# SD.net
KiCad netlist of a schematic drawn in Altium Designer
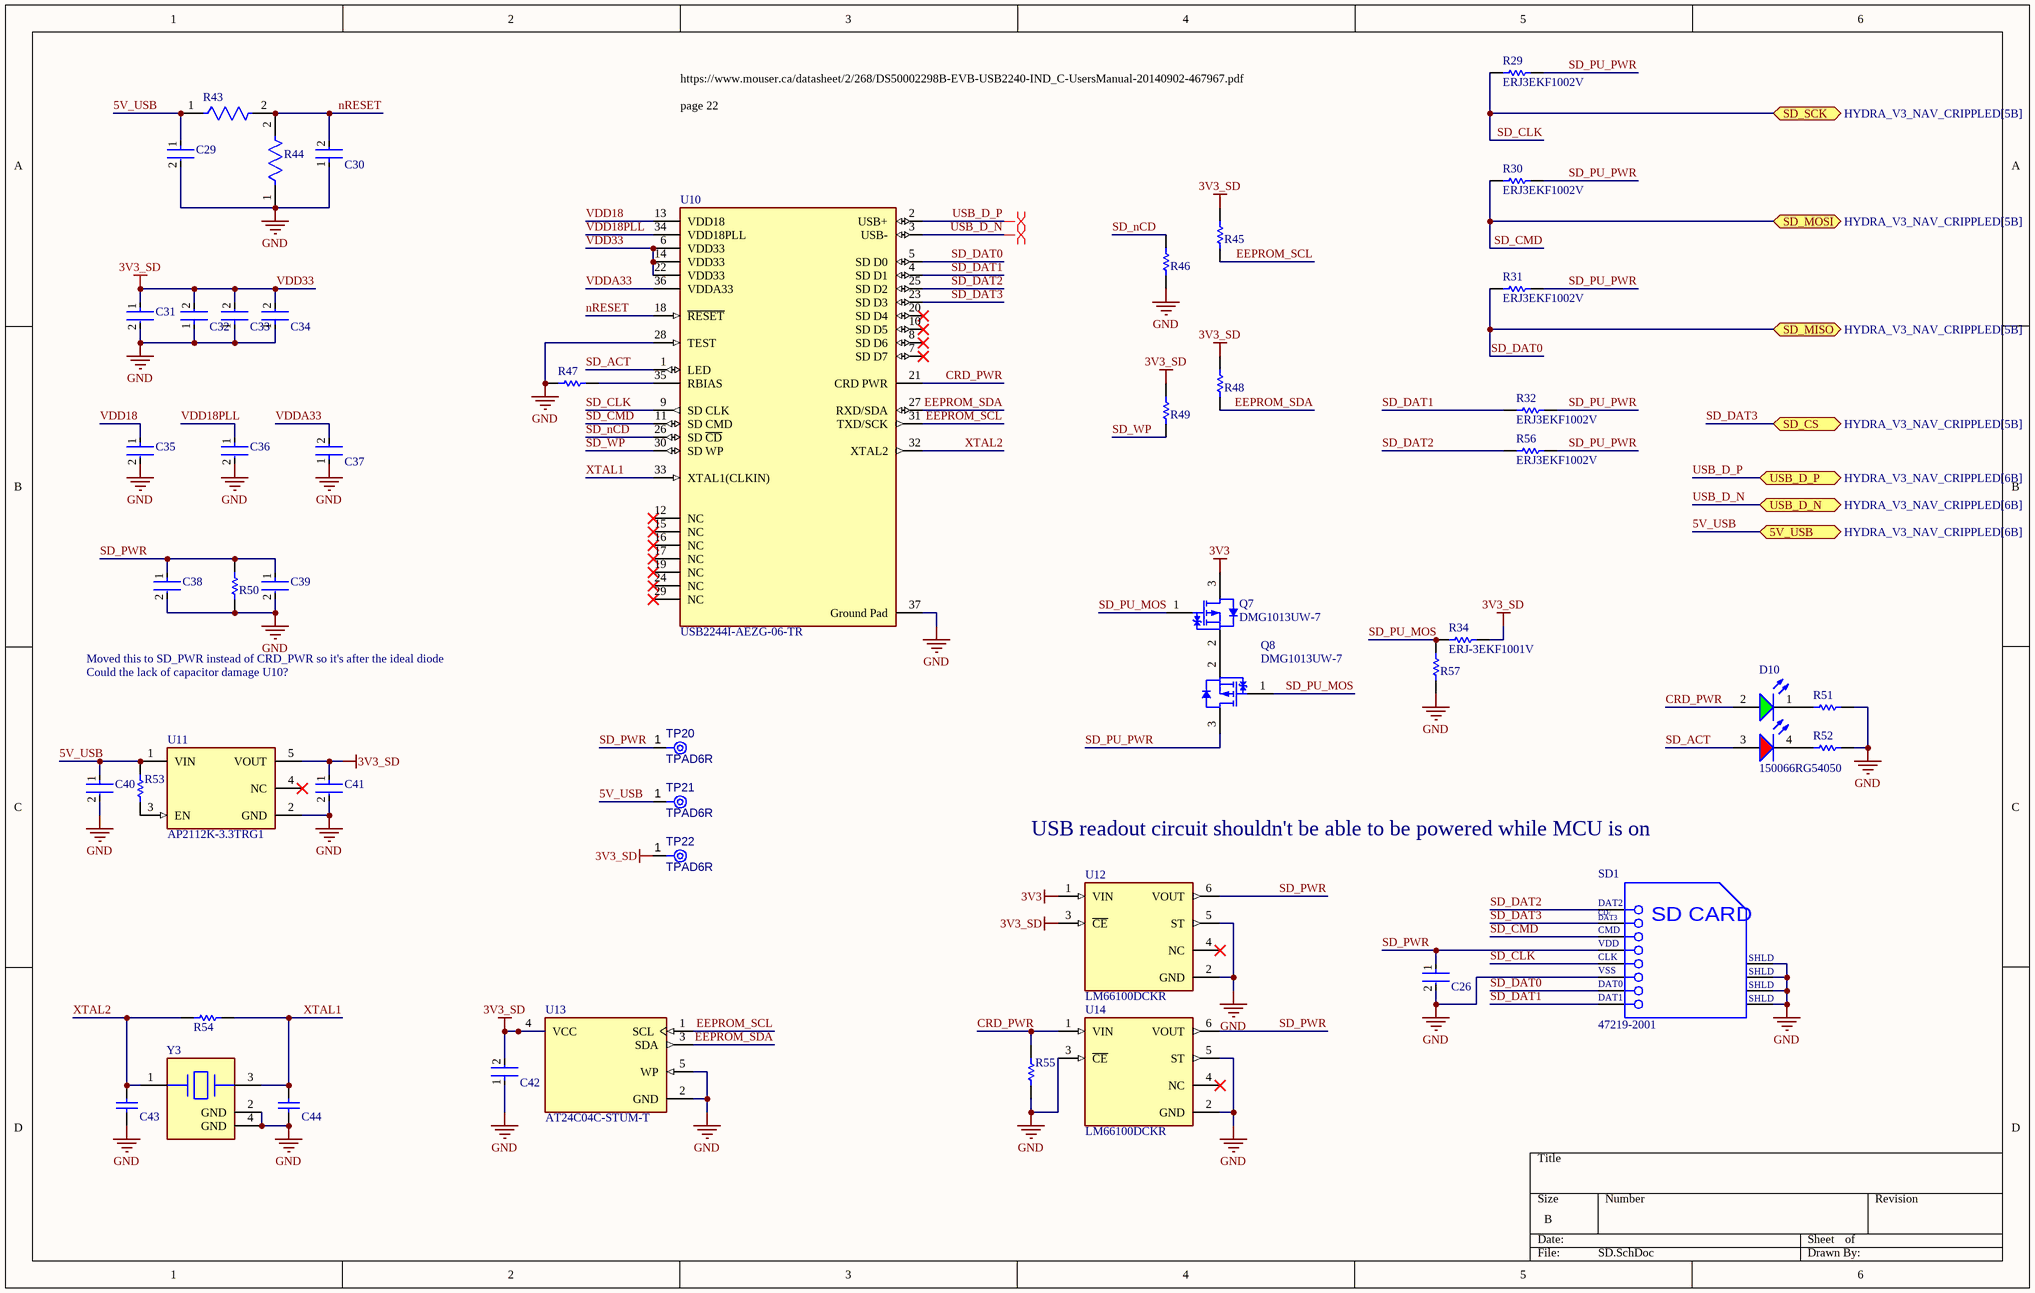
[diagram p0: SD.SchDoc]

(export (version "E")
  (design (tool "Eeschema 10.0.6"))
  (components
    (comp (ref "C26")
      (value "C0402C104K8PACTU")
      (footprint "FP-C0402-BB-MFG")
      (description "CAP CER 0.1UF 10V X5R 0402")
      (fields (field (name "MANUFACTURER") "Kemet") (field (name "TOLERANCE") "0.1"))
      (libsource (lib "Altium Content Vault") (part "b4654b650e69147ec39a6b967a45e02"))
    )
    (comp (ref "C29")
      (value "CC0603KRX7R7BB105")
      (footprint "FP-CC0603-DA-MFG")
      (description "CAP CER 1UF 16V X7R 0603")
      (fields (field (name "TOLERANCE") "0.1") (field (name "MANUFACTURER") "YAGEO"))
      (libsource (lib "Altium Content Vault") (part "11868f565c42a9108669ba33697ecf6"))
    )
    (comp (ref "C30")
      (value "C0402C104K8PACTU")
      (footprint "FP-C0402-BB-MFG")
      (description "CAP CER 0.1UF 10V X5R 0402")
      (fields (field (name "MANUFACTURER") "Kemet") (field (name "TOLERANCE") "0.1"))
      (libsource (lib "Altium Content Vault") (part "b4654b650e69147ec39a6b967a45e02"))
    )
    (comp (ref "C31")
      (value "C0603C475K9PACTU")
      (footprint "FP-C0603-CG-MFG")
      (description "CAP CER 4.7UF 6.3V X5R 0603")
      (fields (field (name "TOLERANCE") "10%") (field (name "MANUFACTURER") "Kemet"))
      (libsource (lib "Altium Content Vault") (part "11868f565c42a9108669ba33697ecf6"))
    )
    (comp (ref "C32")
      (value "C0402C104K8PACTU")
      (footprint "FP-C0402-BB-MFG")
      (description "CAP CER 0.1UF 10V X5R 0402")
      (fields (field (name "MANUFACTURER") "Kemet") (field (name "TOLERANCE") "0.1"))
      (libsource (lib "Altium Content Vault") (part "b4654b650e69147ec39a6b967a45e02"))
    )
    (comp (ref "C33")
      (value "C0402C104K8PACTU")
      (footprint "FP-C0402-BB-MFG")
      (description "CAP CER 0.1UF 10V X5R 0402")
      (fields (field (name "MANUFACTURER") "Kemet") (field (name "TOLERANCE") "0.1"))
      (libsource (lib "Altium Content Vault") (part "b4654b650e69147ec39a6b967a45e02"))
    )
    (comp (ref "C34")
      (value "C0402C104K8PACTU")
      (footprint "FP-C0402-BB-MFG")
      (description "CAP CER 0.1UF 10V X5R 0402")
      (fields (field (name "MANUFACTURER") "Kemet") (field (name "TOLERANCE") "0.1"))
      (libsource (lib "Altium Content Vault") (part "b4654b650e69147ec39a6b967a45e02"))
    )
    (comp (ref "C35")
      (value "CC0603KRX7R7BB105")
      (footprint "FP-CC0603-DA-MFG")
      (description "CAP CER 1UF 16V X7R 0603")
      (fields (field (name "TOLERANCE") "0.1") (field (name "MANUFACTURER") "YAGEO"))
      (libsource (lib "Altium Content Vault") (part "11868f565c42a9108669ba33697ecf6"))
    )
    (comp (ref "C36")
      (value "CC0603KRX7R7BB105")
      (footprint "FP-CC0603-DA-MFG")
      (description "CAP CER 1UF 16V X7R 0603")
      (fields (field (name "TOLERANCE") "0.1") (field (name "MANUFACTURER") "YAGEO"))
      (libsource (lib "Altium Content Vault") (part "11868f565c42a9108669ba33697ecf6"))
    )
    (comp (ref "C37")
      (value "C0402C104K8PACTU")
      (footprint "FP-C0402-BB-MFG")
      (description "CAP CER 0.1UF 10V X5R 0402")
      (fields (field (name "MANUFACTURER") "Kemet") (field (name "TOLERANCE") "0.1"))
      (libsource (lib "Altium Content Vault") (part "b4654b650e69147ec39a6b967a45e02"))
    )
    (comp (ref "C38")
      (value "C0603C475K9PACTU")
      (footprint "FP-C0603-CG-MFG")
      (description "CAP CER 4.7UF 6.3V X5R 0603")
      (fields (field (name "TOLERANCE") "10%") (field (name "MANUFACTURER") "Kemet"))
      (libsource (lib "Altium Content Vault") (part "11868f565c42a9108669ba33697ecf6"))
    )
    (comp (ref "C39")
      (value "CC0603KRX7R9BB102")
      (footprint "FP-CC0603-DA-MFG")
      (description "CAP CER 1000PF 50V X7R 0603")
      (fields
        (field (name "MANUFACTURER") "YAGEO")
        (field (name "OCTOPART") "https://octopart.com/cc0603krx7r9bb102-yageo-192933")
      )
      (libsource (lib "Altium Content Vault") (part "11868f565c42a9108669ba33697ecf6"))
    )
    (comp (ref "C40")
      (value "CC0603KRX7R7BB105")
      (footprint "FP-CC0603-DA-MFG")
      (description "CAP CER 1UF 16V X7R 0603")
      (fields (field (name "TOLERANCE") "0.1") (field (name "MANUFACTURER") "YAGEO"))
      (libsource (lib "Altium Content Vault") (part "11868f565c42a9108669ba33697ecf6"))
    )
    (comp (ref "C41")
      (value "CC0603KRX7R7BB105")
      (footprint "FP-CC0603-DA-MFG")
      (description "CAP CER 1UF 16V X7R 0603")
      (fields (field (name "TOLERANCE") "0.1") (field (name "MANUFACTURER") "YAGEO"))
      (libsource (lib "Altium Content Vault") (part "11868f565c42a9108669ba33697ecf6"))
    )
    (comp (ref "C42")
      (value "C0402C104K8PACTU")
      (footprint "FP-C0402-BB-MFG")
      (description "CAP CER 0.1UF 10V X5R 0402")
      (fields (field (name "MANUFACTURER") "Kemet") (field (name "TOLERANCE") "0.1"))
      (libsource (lib "Altium Content Vault") (part "b4654b650e69147ec39a6b967a45e02"))
    )
    (comp (ref "C43")
      (value "CC0603JRNPO9BN180")
      (footprint "CAPC1608X90X40LL10T20")
      (description "Chip Capacitor, 18 pF, +/- 5%, 50 V, -55 to 125 degC, 0603 (1608 Metric), RoHS, Tape and Reel")
      (fields (field (name "TOLERANCE") "1%"))
      (libsource (lib "Altium Content Vault") (part "CAP-NP-2"))
    )
    (comp (ref "C44")
      (value "CC0603JRNPO9BN180")
      (footprint "CAPC1608X90X40LL10T20")
      (description "Chip Capacitor, 18 pF, +/- 5%, 50 V, -55 to 125 degC, 0603 (1608 Metric), RoHS, Tape and Reel")
      (fields (field (name "TOLERANCE") "1%"))
      (libsource (lib "Altium Content Vault") (part "CAP-NP-2"))
    )
    (comp (ref "D10")
      (value "150066RG54050")
      (footprint "WL-SBCD_0606")
      (description "Led, Red/Grn, 180Mcd/230Mcd, 624Nm/525Nm Rohs Compliant: Yes")
      (libsource (lib "uORocketry Hardware") (part "WL-SBCD_0606_Red & Green"))
    )
    (comp (ref "Q7")
      (value "DMG1013UW-7")
      (footprint "DIOD-SOT323-3_V")
      (fields (field (name "MANUFACTURER") "Diodes Inc"))
      (libsource (lib "Altium Content Vault") (part "PEMOS-GSD-3_C"))
    )
    (comp (ref "Q8")
      (value "DMG1013UW-7")
      (footprint "DIOD-SOT323-3_V")
      (fields (field (name "MANUFACTURER") "Diodes Inc"))
      (libsource (lib "Altium Content Vault") (part "PEMOS-GSD-3_C"))
    )
    (comp (ref "R29")
      (value "ERJ3EKF1002V")
      (footprint "RESC1609X55X30LL15T15")
      (description "Chip Resistor, 10 KOhm, +/- 1%, 0.1 W, -55 to 155 degC, 0603 (1608 Metric), RoHS, Tape and Reel")
      (fields (field (name "TOLERANCE") "1%") (field (name "MANUFACTURER") "Panasonic"))
      (libsource (lib "Altium Content Vault") (part "RES-2"))
    )
    (comp (ref "R30")
      (value "ERJ3EKF1002V")
      (footprint "RESC1609X55X30LL15T15")
      (description "Chip Resistor, 10 KOhm, +/- 1%, 0.1 W, -55 to 155 degC, 0603 (1608 Metric), RoHS, Tape and Reel")
      (fields (field (name "TOLERANCE") "1%") (field (name "MANUFACTURER") "Panasonic"))
      (libsource (lib "Altium Content Vault") (part "RES-2"))
    )
    (comp (ref "R31")
      (value "ERJ3EKF1002V")
      (footprint "RESC1609X55X30LL15T15")
      (description "Chip Resistor, 10 KOhm, +/- 1%, 0.1 W, -55 to 155 degC, 0603 (1608 Metric), RoHS, Tape and Reel")
      (fields (field (name "TOLERANCE") "1%") (field (name "MANUFACTURER") "Panasonic"))
      (libsource (lib "Altium Content Vault") (part "RES-2"))
    )
    (comp (ref "R32")
      (value "ERJ3EKF1002V")
      (footprint "RESC1609X55X30LL15T15")
      (description "Chip Resistor, 10 KOhm, +/- 1%, 0.1 W, -55 to 155 degC, 0603 (1608 Metric), RoHS, Tape and Reel")
      (fields (field (name "TOLERANCE") "1%") (field (name "MANUFACTURER") "Panasonic"))
      (libsource (lib "Altium Content Vault") (part "RES-2"))
    )
    (comp (ref "R34")
      (value "ERJ-3EKF1001V")
      (footprint "RESC1608X55X30LL15T15")
      (fields (field (name "MANUFACTURER") "Panasonic"))
      (libsource (lib "Altium Content Vault") (part "RES"))
    )
    (comp (ref "R43")
      (value "RC0603FR-07100KL")
      (footprint "FP-RC0603-0_55-MFG")
      (description "RES SMD 100K OHM 1% 1/10W 0603")
      (fields (field (name "TOLERANCE") "1%"))
      (libsource (lib "Altium Content Vault") (part "1029c3af85768c4190bb7ad29bc67b5"))
    )
    (comp (ref "R44")
      (value "RC0603FR-07100KL")
      (footprint "FP-RC0603-0_55-MFG")
      (description "RES SMD 100K OHM 1% 1/10W 0603")
      (fields (field (name "TOLERANCE") "1%"))
      (libsource (lib "Altium Content Vault") (part "1029c3af85768c4190bb7ad29bc67b5"))
    )
    (comp (ref "R45")
      (value "ERJ3EKF1002V")
      (footprint "RESC1609X55X30LL15T15")
      (description "Chip Resistor, 10 KOhm, +/- 1%, 0.1 W, -55 to 155 degC, 0603 (1608 Metric), RoHS, Tape and Reel")
      (fields (field (name "TOLERANCE") "1%") (field (name "MANUFACTURER") "Panasonic"))
      (libsource (lib "Altium Content Vault") (part "RES-2"))
    )
    (comp (ref "R46")
      (value "ERJ3EKF1002V")
      (footprint "RESC1609X55X30LL15T15")
      (description "Chip Resistor, 10 KOhm, +/- 1%, 0.1 W, -55 to 155 degC, 0603 (1608 Metric), RoHS, Tape and Reel")
      (fields (field (name "TOLERANCE") "1%") (field (name "MANUFACTURER") "Panasonic"))
      (libsource (lib "Altium Content Vault") (part "RES-2"))
    )
    (comp (ref "R47")
      (value "RC0603FR-0712KL")
      (footprint "RESC1608X55X25NL10T15")
      (description "Chip Resistor, 12 KOhm, +/- 1%, 100 mW, -55 to 155 degC, 0603 (1608 Metric), RoHS, Tape and Reel")
      (fields (field (name "TOLERANCE") "1%"))
      (libsource (lib "Altium Content Vault") (part "RES-2"))
    )
    (comp (ref "R48")
      (value "ERJ3EKF1002V")
      (footprint "RESC1609X55X30LL15T15")
      (description "Chip Resistor, 10 KOhm, +/- 1%, 0.1 W, -55 to 155 degC, 0603 (1608 Metric), RoHS, Tape and Reel")
      (fields (field (name "TOLERANCE") "1%") (field (name "MANUFACTURER") "Panasonic"))
      (libsource (lib "Altium Content Vault") (part "RES-2"))
    )
    (comp (ref "R49")
      (value "ERJ3EKF1002V")
      (footprint "RESC1609X55X30LL15T15")
      (description "Chip Resistor, 10 KOhm, +/- 1%, 0.1 W, -55 to 155 degC, 0603 (1608 Metric), RoHS, Tape and Reel")
      (fields (field (name "TOLERANCE") "1%") (field (name "MANUFACTURER") "Panasonic"))
      (libsource (lib "Altium Content Vault") (part "RES-2"))
    )
    (comp (ref "R50")
      (value "ERJ3EKF2201V")
      (footprint "RESC1608X55X30LL15T15")
      (fields (field (name "MANUFACTURER") "Panasonic"))
      (libsource (lib "Altium Content Vault") (part "RES"))
    )
    (comp (ref "R51")
      (value "ERJ-3EKF3300V")
      (footprint "RESC1608X55X30LL15T15")
      (description "Chip Resistor, 330 Ohm, +/- 1%, 0.1 W, -55 to 155 degC, 0603 (1608 Metric), RoHS, Tape and Reel")
      (libsource (lib "Altium Content Vault") (part "RES-2"))
    )
    (comp (ref "R52")
      (value "ERJ-3EKF3300V")
      (footprint "RESC1608X55X30LL15T15")
      (description "Chip Resistor, 330 Ohm, +/- 1%, 0.1 W, -55 to 155 degC, 0603 (1608 Metric), RoHS, Tape and Reel")
      (libsource (lib "Altium Content Vault") (part "RES-2"))
    )
    (comp (ref "R53")
      (value "ERJ3EKF1002V")
      (footprint "RESC1609X55X30LL15T15")
      (description "Chip Resistor, 10 KOhm, +/- 1%, 0.1 W, -55 to 155 degC, 0603 (1608 Metric), RoHS, Tape and Reel")
      (fields (field (name "TOLERANCE") "1%") (field (name "MANUFACTURER") "Panasonic"))
      (libsource (lib "Altium Content Vault") (part "RES-2"))
    )
    (comp (ref "R54")
      (value "RT0603BRD071ML")
      (footprint "RESC1608X55X30NL20T20")
      (fields (field (name "MANUFACTURER") "Panasonic") (field (name "PART NUMBER") "ERA-3AEB163V"))
      (libsource (lib "Altium Content Vault") (part "RES"))
    )
    (comp (ref "R55")
      (value "ERJ3EKF1002V")
      (footprint "RESC1609X55X30LL15T15")
      (description "Chip Resistor, 10 KOhm, +/- 1%, 0.1 W, -55 to 155 degC, 0603 (1608 Metric), RoHS, Tape and Reel")
      (fields (field (name "TOLERANCE") "1%") (field (name "MANUFACTURER") "Panasonic"))
      (libsource (lib "Altium Content Vault") (part "RES-2"))
    )
    (comp (ref "R56")
      (value "ERJ3EKF1002V")
      (footprint "RESC1609X55X30LL15T15")
      (description "Chip Resistor, 10 KOhm, +/- 1%, 0.1 W, -55 to 155 degC, 0603 (1608 Metric), RoHS, Tape and Reel")
      (fields (field (name "TOLERANCE") "1%") (field (name "MANUFACTURER") "Panasonic"))
      (libsource (lib "Altium Content Vault") (part "RES-2"))
    )
    (comp (ref "R57")
      (value "ERJ3EKF1002V")
      (footprint "RESC1609X55X30LL15T15")
      (description "Chip Resistor, 10 KOhm, +/- 1%, 0.1 W, -55 to 155 degC, 0603 (1608 Metric), RoHS, Tape and Reel")
      (fields (field (name "TOLERANCE") "1%") (field (name "MANUFACTURER") "Panasonic"))
      (libsource (lib "Altium Content Vault") (part "RES-2"))
    )
    (comp (ref "SD1")
      (value "47219-2001")
      (footprint "MOLX-47219-2001-8_V")
      (description "MicroSD Card Connector, Hinge Type, -40 to 85 degC, 8-Pin SMD, RoHS, Tape and Reel")
      (fields (field (name "MANUFACTURER") "Molex"))
      (libsource (lib "Altium Content Vault") (part "CN-SD-8-4S"))
    )
    (comp (ref "TP20")
      (value "TPAD6R")
      (footprint "TP06R")
      (description "0.6mm round")
      (libsource (lib "uORocketry Hardware") (part "CMP-001-0001-4"))
    )
    (comp (ref "TP21")
      (value "TPAD6R")
      (footprint "TP06R")
      (description "0.6mm round")
      (libsource (lib "uORocketry Hardware") (part "CMP-001-0001-4"))
    )
    (comp (ref "TP22")
      (value "TPAD6R")
      (footprint "TP06R")
      (description "0.6mm round")
      (libsource (lib "uORocketry Hardware") (part "CMP-001-0001-4"))
    )
    (comp (ref "U10")
      (value "USB2244I-AEZG-06-TR")
      (footprint "FP-36QFN-4106-6x6B-MFG")
      (description "IC USB FLASH MEDIA CTRLR 36QFN")
      (fields
        (field (name "OCTOPART") "https://octopart.com/usb2244i-aezg-06-tr-microchip-34964624")
        (field (name "MANUFACTURER") "Microchip")
      )
      (libsource (lib "Altium Content Vault") (part "7e0b9f2b1d466ebfa159a9011d5350a"))
    )
    (comp (ref "U11")
      (value "AP2112K-3.3TRG1")
      (footprint "FP-SOT25-IPC_A")
      (description "IC REG LINEAR 3.3V 600MA SOT25")
      (libsource (lib "Altium Content Vault") (part "c8ab751aee5229183125ab046a11caa"))
    )
    (comp (ref "U12")
      (value "LM66100DCKR")
      (footprint "LM66100DCKR-Footprint-1")
      (description "1.5-V to 5.5-V, 1.5-A, 0.5-uA IQ ideal diode with Integrated FET 6-SC70 -40 to 105")
      (libsource (lib "uORocketry Hardware") (part "LM66100DCKR"))
    )
    (comp (ref "U13")
      (value "AT24C04C-STUM-T")
      (footprint "FP-C04-21344-IPC_C")
      (description "IC EEPROM 4KBIT I2C 1MHZ SOT23-5")
      (libsource (lib "Altium Content Vault") (part "b7b3c71dee7af76d4cfe2c012f9ae10"))
    )
    (comp (ref "U14")
      (value "LM66100DCKR")
      (footprint "LM66100DCKR-Footprint-1")
      (description "1.5-V to 5.5-V, 1.5-A, 0.5-uA IQ ideal diode with Integrated FET 6-SC70 -40 to 105")
      (libsource (lib "uORocketry Hardware") (part "LM66100DCKR"))
    )
    (comp (ref "Y3")
      (value "ABM8AIG-24.000MHZ-12-2Z-T3")
      (footprint "FP-ABM8AIG-MFG")
      (description "Crystal 24MHz ±20ppm (Tol) ±50ppm (Stability) 12pF FUND 50Ω Automotive 4-Pin Ultra Mini-CSMD T/R")
      (libsource (lib "Altium Content Vault") (part "5645ab55de99a04feaa93ac4102b7fe"))
    )
  )
  (nets
    (net (code "1") (name "/5V_USB") (class "Default")
      (node (ref "C29") (pin "1") (pinfunction "1_1") (pintype "passive"))
      (node (ref "C40") (pin "1") (pinfunction "1_1") (pintype "passive"))
      (node (ref "R43") (pin "1") (pinfunction "1_1") (pintype "passive"))
      (node (ref "R53") (pin "2") (pinfunction "2_2") (pintype "passive"))
      (node (ref "TP21") (pin "1") (pinfunction "TP_1") (pintype "passive"))
      (node (ref "U11") (pin "1") (pinfunction "VIN_1") (pintype "power_in"))
    )
    (net (code "2") (name "/CRD_PWR") (class "Default")
      (node (ref "D10") (pin "2") (pinfunction "A_2") (pintype "passive"))
      (node (ref "R55") (pin "2") (pinfunction "2_2") (pintype "passive"))
      (node (ref "U10") (pin "21") (pinfunction "CRD_PWR_21") (pintype "power_in"))
      (node (ref "U14") (pin "1") (pinfunction "VIN_1") (pintype "input"))
    )
    (net (code "3") (name "/EEPROM_SCL") (class "Default")
      (node (ref "R45") (pin "1") (pinfunction "1_1") (pintype "passive"))
      (node (ref "U10") (pin "31") (pinfunction "TXD/SCK_31") (pintype "output"))
      (node (ref "U13") (pin "1") (pinfunction "SCL_1") (pintype "input"))
    )
    (net (code "4") (name "/EEPROM_SDA") (class "Default")
      (node (ref "R48") (pin "1") (pinfunction "1_1") (pintype "passive"))
      (node (ref "U10") (pin "27") (pinfunction "RXD/SDA_27") (pintype "bidirectional"))
      (node (ref "U13") (pin "3") (pinfunction "SDA_3") (pintype "output"))
    )
    (net (code "5") (name "/SD_ACT") (class "Default")
      (node (ref "D10") (pin "3") (pinfunction "A_3") (pintype "passive"))
      (node (ref "U10") (pin "1") (pinfunction "LED_1") (pintype "bidirectional"))
    )
    (net (code "6") (name "/SD_CLK") (class "Default")
      (node (ref "R29") (pin "1") (pinfunction "1_1") (pintype "passive"))
      (node (ref "SD1") (pin "5") (pinfunction "CLK_5") (pintype "passive"))
      (node (ref "U10") (pin "9") (pinfunction "SD_CLK_9") (pintype "output"))
    )
    (net (code "7") (name "/SD_CMD") (class "Default")
      (node (ref "R30") (pin "1") (pinfunction "1_1") (pintype "passive"))
      (node (ref "SD1") (pin "3") (pinfunction "CMD_3") (pintype "passive"))
      (node (ref "U10") (pin "11") (pinfunction "SD_CMD_11") (pintype "bidirectional"))
    )
    (net (code "8") (name "/SD_DAT0") (class "Default")
      (node (ref "R31") (pin "1") (pinfunction "1_1") (pintype "passive"))
      (node (ref "SD1") (pin "7") (pinfunction "DAT0_7") (pintype "passive"))
      (node (ref "U10") (pin "5") (pinfunction "SD_D0_5") (pintype "bidirectional"))
    )
    (net (code "9") (name "/SD_DAT1") (class "Default")
      (node (ref "R32") (pin "1") (pinfunction "1_1") (pintype "passive"))
      (node (ref "SD1") (pin "8") (pinfunction "DAT1_8") (pintype "passive"))
      (node (ref "U10") (pin "4") (pinfunction "SD_D1_4") (pintype "bidirectional"))
    )
    (net (code "10") (name "/SD_DAT2") (class "Default")
      (node (ref "R56") (pin "1") (pinfunction "1_1") (pintype "passive"))
      (node (ref "SD1") (pin "1") (pinfunction "DAT2_1") (pintype "passive"))
      (node (ref "U10") (pin "25") (pinfunction "SD_D2_25") (pintype "bidirectional"))
    )
    (net (code "11") (name "/SD_DAT3") (class "Default")
      (node (ref "SD1") (pin "2") (pinfunction "CD/DAT3_2") (pintype "passive"))
      (node (ref "U10") (pin "23") (pinfunction "SD_D3_23") (pintype "bidirectional"))
    )
    (net (code "12") (name "/SD_PU_MOS") (class "Default")
      (node (ref "Q7") (pin "1") (pinfunction "G_1") (pintype "passive"))
      (node (ref "Q8") (pin "1") (pinfunction "G_1") (pintype "passive"))
      (node (ref "R34") (pin "1") (pinfunction "1_1") (pintype "passive"))
      (node (ref "R57") (pin "2") (pinfunction "2_2") (pintype "passive"))
    )
    (net (code "13") (name "/SD_PU_PWR") (class "Default")
      (node (ref "Q8") (pin "3") (pinfunction "D_3") (pintype "passive"))
      (node (ref "R29") (pin "2") (pinfunction "2_2") (pintype "passive"))
      (node (ref "R30") (pin "2") (pinfunction "2_2") (pintype "passive"))
      (node (ref "R31") (pin "2") (pinfunction "2_2") (pintype "passive"))
      (node (ref "R32") (pin "2") (pinfunction "2_2") (pintype "passive"))
      (node (ref "R56") (pin "2") (pinfunction "2_2") (pintype "passive"))
    )
    (net (code "14") (name "/SD_PWR") (class "Default")
      (node (ref "C26") (pin "1") (pinfunction "1_1") (pintype "passive"))
      (node (ref "C38") (pin "1") (pinfunction "1_1") (pintype "passive"))
      (node (ref "C39") (pin "1") (pinfunction "1_1") (pintype "passive"))
      (node (ref "R50") (pin "2") (pinfunction "2_2") (pintype "passive"))
      (node (ref "SD1") (pin "4") (pinfunction "VDD_4") (pintype "passive"))
      (node (ref "TP20") (pin "1") (pinfunction "TP_1") (pintype "passive"))
      (node (ref "U12") (pin "6") (pinfunction "VOUT_6") (pintype "output"))
      (node (ref "U14") (pin "6") (pinfunction "VOUT_6") (pintype "output"))
    )
    (net (code "15") (name "/SD_WP") (class "Default")
      (node (ref "R49") (pin "1") (pinfunction "1_1") (pintype "passive"))
      (node (ref "U10") (pin "30") (pinfunction "SD_WP_30") (pintype "bidirectional"))
    )
    (net (code "16") (name "/SD_nCD") (class "Default")
      (node (ref "R46") (pin "2") (pinfunction "2_2") (pintype "passive"))
      (node (ref "U10") (pin "26") (pinfunction "SD_~{CD}_26") (pintype "bidirectional"))
    )
    (net (code "17") (name "/USB_D_N") (class "Default")
      (node (ref "U10") (pin "3") (pinfunction "USB-_3") (pintype "bidirectional"))
    )
    (net (code "18") (name "/USB_D_P") (class "Default")
      (node (ref "U10") (pin "2") (pinfunction "USB+_2") (pintype "bidirectional"))
    )
    (net (code "19") (name "/VDD18") (class "Default")
      (node (ref "C35") (pin "1") (pinfunction "1_1") (pintype "passive"))
      (node (ref "U10") (pin "13") (pinfunction "VDD18_13") (pintype "power_in"))
    )
    (net (code "20") (name "/VDD18PLL") (class "Default")
      (node (ref "C36") (pin "1") (pinfunction "1_1") (pintype "passive"))
      (node (ref "U10") (pin "34") (pinfunction "VDD18PLL_34") (pintype "power_in"))
    )
    (net (code "21") (name "/VDDA33") (class "Default")
      (node (ref "C37") (pin "2") (pinfunction "2_2") (pintype "passive"))
      (node (ref "U10") (pin "36") (pinfunction "VDDA33_36") (pintype "power_in"))
    )
    (net (code "22") (name "/XTAL1") (class "Default")
      (node (ref "C44") (pin "2") (pinfunction "2_2") (pintype "passive"))
      (node (ref "R54") (pin "1") (pinfunction "1_1") (pintype "passive"))
      (node (ref "U10") (pin "33") (pinfunction "XTAL1(CLKIN)_33") (pintype "input"))
      (node (ref "Y3") (pin "3") (pinfunction "3_3") (pintype "passive"))
    )
    (net (code "23") (name "/XTAL2") (class "Default")
      (node (ref "C43") (pin "2") (pinfunction "2_2") (pintype "passive"))
      (node (ref "R54") (pin "2") (pinfunction "2_2") (pintype "passive"))
      (node (ref "U10") (pin "32") (pinfunction "XTAL2_32") (pintype "output"))
      (node (ref "Y3") (pin "1") (pinfunction "1_1") (pintype "passive"))
    )
    (net (code "24") (name "/nRESET") (class "Default")
      (node (ref "C30") (pin "2") (pinfunction "2_2") (pintype "passive"))
      (node (ref "R43") (pin "2") (pinfunction "2_2") (pintype "passive"))
      (node (ref "R44") (pin "2") (pinfunction "2_2") (pintype "passive"))
      (node (ref "U10") (pin "18") (pinfunction "~{RESET}_18") (pintype "input"))
    )
    (net (code "25") (name "3V3") (class "Default")
      (node (ref "Q7") (pin "3") (pinfunction "D_3") (pintype "passive"))
      (node (ref "U12") (pin "1") (pinfunction "VIN_1") (pintype "input"))
    )
    (net (code "26") (name "3V3_SD") (class "Default")
      (node (ref "C31") (pin "1") (pinfunction "1_1") (pintype "passive"))
      (node (ref "C32") (pin "2") (pinfunction "2_2") (pintype "passive"))
      (node (ref "C33") (pin "2") (pinfunction "2_2") (pintype "passive"))
      (node (ref "C34") (pin "2") (pinfunction "2_2") (pintype "passive"))
      (node (ref "C41") (pin "1") (pinfunction "1_1") (pintype "passive"))
      (node (ref "C42") (pin "2") (pinfunction "2_2") (pintype "passive"))
      (node (ref "R34") (pin "2") (pinfunction "2_2") (pintype "passive"))
      (node (ref "R45") (pin "2") (pinfunction "2_2") (pintype "passive"))
      (node (ref "R48") (pin "2") (pinfunction "2_2") (pintype "passive"))
      (node (ref "R49") (pin "2") (pinfunction "2_2") (pintype "passive"))
      (node (ref "TP22") (pin "1") (pinfunction "TP_1") (pintype "passive"))
      (node (ref "U10") (pin "14") (pinfunction "VDD33_14") (pintype "power_in"))
      (node (ref "U10") (pin "22") (pinfunction "VDD33_22") (pintype "power_in"))
      (node (ref "U10") (pin "6") (pinfunction "VDD33_6") (pintype "power_in"))
      (node (ref "U11") (pin "5") (pinfunction "VOUT_5") (pintype "power_in"))
      (node (ref "U12") (pin "3") (pinfunction "~{CE}_3") (pintype "input"))
      (node (ref "U13") (pin "4") (pinfunction "VCC_4") (pintype "power_in"))
    )
    (net (code "27") (name "GND") (class "Default")
      (node (ref "C26") (pin "2") (pinfunction "2_2") (pintype "passive"))
      (node (ref "C29") (pin "2") (pinfunction "2_2") (pintype "passive"))
      (node (ref "C30") (pin "1") (pinfunction "1_1") (pintype "passive"))
      (node (ref "C31") (pin "2") (pinfunction "2_2") (pintype "passive"))
      (node (ref "C32") (pin "1") (pinfunction "1_1") (pintype "passive"))
      (node (ref "C33") (pin "1") (pinfunction "1_1") (pintype "passive"))
      (node (ref "C34") (pin "1") (pinfunction "1_1") (pintype "passive"))
      (node (ref "C35") (pin "2") (pinfunction "2_2") (pintype "passive"))
      (node (ref "C36") (pin "2") (pinfunction "2_2") (pintype "passive"))
      (node (ref "C37") (pin "1") (pinfunction "1_1") (pintype "passive"))
      (node (ref "C38") (pin "2") (pinfunction "2_2") (pintype "passive"))
      (node (ref "C39") (pin "2") (pinfunction "2_2") (pintype "passive"))
      (node (ref "C40") (pin "2") (pinfunction "2_2") (pintype "passive"))
      (node (ref "C41") (pin "2") (pinfunction "2_2") (pintype "passive"))
      (node (ref "C42") (pin "1") (pinfunction "1_1") (pintype "passive"))
      (node (ref "C43") (pin "1") (pinfunction "1_1") (pintype "passive"))
      (node (ref "C44") (pin "1") (pinfunction "1_1") (pintype "passive"))
      (node (ref "R44") (pin "1") (pinfunction "1_1") (pintype "passive"))
      (node (ref "R46") (pin "1") (pinfunction "1_1") (pintype "passive"))
      (node (ref "R47") (pin "1") (pinfunction "1_1") (pintype "passive"))
      (node (ref "R50") (pin "1") (pinfunction "1_1") (pintype "passive"))
      (node (ref "R51") (pin "2") (pinfunction "2_2") (pintype "passive"))
      (node (ref "R52") (pin "2") (pinfunction "2_2") (pintype "passive"))
      (node (ref "R55") (pin "1") (pinfunction "1_1") (pintype "passive"))
      (node (ref "R57") (pin "1") (pinfunction "1_1") (pintype "passive"))
      (node (ref "SD1") (pin "10") (pinfunction "SHLD_10") (pintype "passive"))
      (node (ref "SD1") (pin "11") (pinfunction "SHLD_11") (pintype "passive"))
      (node (ref "SD1") (pin "12") (pinfunction "SHLD_12") (pintype "passive"))
      (node (ref "SD1") (pin "6") (pinfunction "VSS_6") (pintype "passive"))
      (node (ref "SD1") (pin "9") (pinfunction "SHLD_9") (pintype "passive"))
      (node (ref "U10") (pin "28") (pinfunction "TEST_28") (pintype "input"))
      (node (ref "U10") (pin "37") (pinfunction "Ground_Pad_37") (pintype "power_in"))
      (node (ref "U11") (pin "2") (pinfunction "GND_2") (pintype "power_in"))
      (node (ref "U12") (pin "2") (pinfunction "GND_2") (pintype "power_in"))
      (node (ref "U12") (pin "5") (pinfunction "ST_5") (pintype "output"))
      (node (ref "U13") (pin "2") (pinfunction "GND_2") (pintype "power_in"))
      (node (ref "U13") (pin "5") (pinfunction "WP_5") (pintype "input"))
      (node (ref "U14") (pin "2") (pinfunction "GND_2") (pintype "power_in"))
      (node (ref "U14") (pin "3") (pinfunction "~{CE}_3") (pintype "input"))
      (node (ref "U14") (pin "5") (pinfunction "ST_5") (pintype "output"))
      (node (ref "Y3") (pin "2") (pinfunction "GND_2") (pintype "power_in"))
      (node (ref "Y3") (pin "4") (pinfunction "GND_4") (pintype "power_in"))
    )
    (net (code "28") (name "Net-(D10-K-Pad1)") (class "Default")
      (node (ref "D10") (pin "1") (pinfunction "K_1") (pintype "passive"))
      (node (ref "R51") (pin "1") (pinfunction "1_1") (pintype "passive"))
    )
    (net (code "29") (name "Net-(D10-K-Pad4)") (class "Default")
      (node (ref "D10") (pin "4") (pinfunction "K_4") (pintype "passive"))
      (node (ref "R52") (pin "1") (pinfunction "1_1") (pintype "passive"))
    )
    (net (code "30") (name "Net-(Q7-S)") (class "Default")
      (node (ref "Q7") (pin "2") (pinfunction "S_2") (pintype "passive"))
      (node (ref "Q8") (pin "2") (pinfunction "S_2") (pintype "passive"))
    )
    (net (code "31") (name "Net-(U10-RBIAS)") (class "Default")
      (node (ref "R47") (pin "2") (pinfunction "2_2") (pintype "passive"))
      (node (ref "U10") (pin "35") (pinfunction "RBIAS_35") (pintype "passive"))
    )
    (net (code "32") (name "Net-(U11-EN)") (class "Default")
      (node (ref "R53") (pin "1") (pinfunction "1_1") (pintype "passive"))
      (node (ref "U11") (pin "3") (pinfunction "EN_3") (pintype "input"))
    )
    (net (code "33") (name "unconnected-(U10-NC-Pad12)") (class "Default")
      (node (ref "U10") (pin "12") (pinfunction "NC_12") (pintype "passive+no_connect"))
    )
    (net (code "34") (name "unconnected-(U10-NC-Pad15)") (class "Default")
      (node (ref "U10") (pin "15") (pinfunction "NC_15") (pintype "passive+no_connect"))
    )
    (net (code "35") (name "unconnected-(U10-NC-Pad16)") (class "Default")
      (node (ref "U10") (pin "16") (pinfunction "NC_16") (pintype "passive+no_connect"))
    )
    (net (code "36") (name "unconnected-(U10-NC-Pad17)") (class "Default")
      (node (ref "U10") (pin "17") (pinfunction "NC_17") (pintype "passive+no_connect"))
    )
    (net (code "37") (name "unconnected-(U10-NC-Pad19)") (class "Default")
      (node (ref "U10") (pin "19") (pinfunction "NC_19") (pintype "passive+no_connect"))
    )
    (net (code "38") (name "unconnected-(U10-NC-Pad24)") (class "Default")
      (node (ref "U10") (pin "24") (pinfunction "NC_24") (pintype "passive+no_connect"))
    )
    (net (code "39") (name "unconnected-(U10-NC-Pad29)") (class "Default")
      (node (ref "U10") (pin "29") (pinfunction "NC_29") (pintype "passive+no_connect"))
    )
    (net (code "40") (name "unconnected-(U10-SD_D4-Pad20)") (class "Default")
      (node (ref "U10") (pin "20") (pinfunction "SD_D4_20") (pintype "bidirectional+no_connect"))
    )
    (net (code "41") (name "unconnected-(U10-SD_D5-Pad10)") (class "Default")
      (node (ref "U10") (pin "10") (pinfunction "SD_D5_10") (pintype "bidirectional+no_connect"))
    )
    (net (code "42") (name "unconnected-(U10-SD_D6-Pad8)") (class "Default")
      (node (ref "U10") (pin "8") (pinfunction "SD_D6_8") (pintype "bidirectional+no_connect"))
    )
    (net (code "43") (name "unconnected-(U10-SD_D7-Pad7)") (class "Default")
      (node (ref "U10") (pin "7") (pinfunction "SD_D7_7") (pintype "bidirectional+no_connect"))
    )
    (net (code "44") (name "unconnected-(U11-NC-Pad4)") (class "Default")
      (node (ref "U11") (pin "4") (pinfunction "NC_4") (pintype "passive+no_connect"))
    )
    (net (code "45") (name "unconnected-(U12-NC-Pad4)") (class "Default")
      (node (ref "U12") (pin "4") (pinfunction "NC_4") (pintype "passive+no_connect"))
    )
    (net (code "46") (name "unconnected-(U14-NC-Pad4)") (class "Default")
      (node (ref "U14") (pin "4") (pinfunction "NC_4") (pintype "passive+no_connect"))
    )
  )
)
